# ESP-12S.net
KiCad netlist of a schematic drawn in Altium Designer
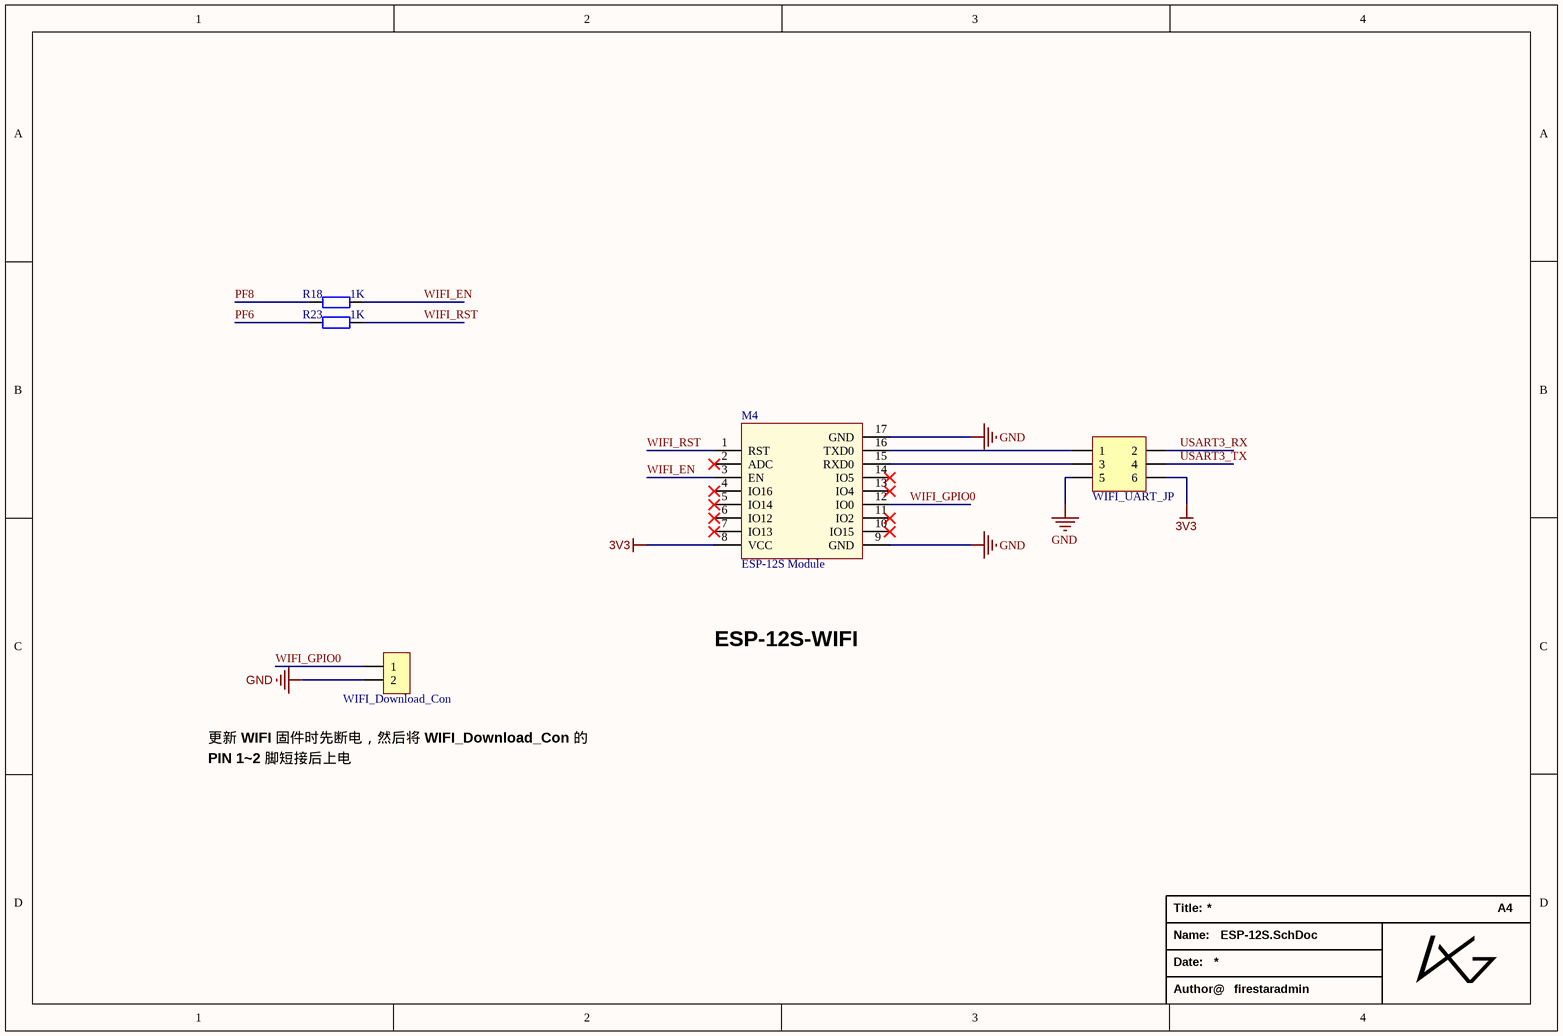
[diagram p0: ESP-12S.SchDoc]

(export (version "E")
  (design (tool "Eeschema 10.0.6"))
  (components
    (comp (ref "M4")
      (value "ESP-12S Module")
      (footprint "ESP-12S Module")
      (libsource (lib "ESP-12S Module") (part "ESP-12S Module"))
    )
    (comp (ref "R18")
      (value "1K")
      (footprint "R 0603_M")
      (description "Resistor")
      (libsource (lib "General") (part "RES"))
    )
    (comp (ref "R23")
      (value "1K")
      (footprint "R 0603_M")
      (description "Resistor")
      (libsource (lib "General") (part "RES"))
    )
    (comp (ref "WIFI_Download_Con")
      (value "HDR-1X2")
      (footprint "HDR2.54-LI-2P")
      (description "2P接插件")
      (fields (field (name "版权归属") "源创客"))
      (libsource (lib "SCH-接插件-脚距2.54") (part "Header 2"))
    )
    (comp (ref "WIFI_UART_JP")
      (value "Header3X2")
      (footprint "HDR2.54-LI-2x3P")
      (description "3*2P接插件")
      (fields (field (name "版权归属") "源创客"))
      (libsource (lib "SCH-接插件-脚距2.54") (part "Header 3X2"))
    )
  )
  (nets
    (net (code "1") (name "/PF6") (class "Default")
      (node (ref "R23") (pin "2") (pinfunction "2_2") (pintype "passive"))
    )
    (net (code "2") (name "/PF8") (class "Default")
      (node (ref "R18") (pin "2") (pinfunction "2_2") (pintype "passive"))
    )
    (net (code "3") (name "/USART3_RX") (class "Default")
      (node (ref "WIFI_UART_JP") (pin "2") (pinfunction "2_2") (pintype "passive"))
    )
    (net (code "4") (name "/USART3_TX") (class "Default")
      (node (ref "WIFI_UART_JP") (pin "4") (pinfunction "4_4") (pintype "passive"))
    )
    (net (code "5") (name "/WIFI_EN") (class "Default")
      (node (ref "M4") (pin "3") (pinfunction "EN_3") (pintype "passive"))
      (node (ref "R18") (pin "1") (pinfunction "1_1") (pintype "passive"))
    )
    (net (code "6") (name "/WIFI_GPIO0") (class "Default")
      (node (ref "M4") (pin "12") (pinfunction "IO0_12") (pintype "passive"))
      (node (ref "WIFI_Download_Con") (pin "1") (pinfunction "1_1") (pintype "passive"))
    )
    (net (code "7") (name "/WIFI_RST") (class "Default")
      (node (ref "M4") (pin "1") (pinfunction "RST_1") (pintype "passive"))
      (node (ref "R23") (pin "1") (pinfunction "1_1") (pintype "passive"))
    )
    (net (code "8") (name "3V3") (class "Default")
      (node (ref "M4") (pin "8") (pinfunction "VCC_8") (pintype "passive"))
      (node (ref "WIFI_UART_JP") (pin "6") (pinfunction "6_6") (pintype "passive"))
    )
    (net (code "9") (name "GND") (class "Default")
      (node (ref "M4") (pin "17") (pinfunction "GND_17") (pintype "passive"))
      (node (ref "M4") (pin "9") (pinfunction "GND_9") (pintype "passive"))
      (node (ref "WIFI_Download_Con") (pin "2") (pinfunction "2_2") (pintype "passive"))
      (node (ref "WIFI_UART_JP") (pin "5") (pinfunction "5_5") (pintype "passive"))
    )
    (net (code "10") (name "Net-(M4-RXD0)") (class "Default")
      (node (ref "M4") (pin "15") (pinfunction "RXD0_15") (pintype "passive"))
      (node (ref "WIFI_UART_JP") (pin "3") (pinfunction "3_3") (pintype "passive"))
    )
    (net (code "11") (name "Net-(M4-TXD0)") (class "Default")
      (node (ref "M4") (pin "16") (pinfunction "TXD0_16") (pintype "passive"))
      (node (ref "WIFI_UART_JP") (pin "1") (pinfunction "1_1") (pintype "passive"))
    )
    (net (code "12") (name "unconnected-(M4-ADC-Pad2)") (class "Default")
      (node (ref "M4") (pin "2") (pinfunction "ADC_2") (pintype "passive+no_connect"))
    )
    (net (code "13") (name "unconnected-(M4-IO2-Pad11)") (class "Default")
      (node (ref "M4") (pin "11") (pinfunction "IO2_11") (pintype "passive+no_connect"))
    )
    (net (code "14") (name "unconnected-(M4-IO4-Pad13)") (class "Default")
      (node (ref "M4") (pin "13") (pinfunction "IO4_13") (pintype "passive+no_connect"))
    )
    (net (code "15") (name "unconnected-(M4-IO5-Pad14)") (class "Default")
      (node (ref "M4") (pin "14") (pinfunction "IO5_14") (pintype "passive+no_connect"))
    )
    (net (code "16") (name "unconnected-(M4-IO12-Pad6)") (class "Default")
      (node (ref "M4") (pin "6") (pinfunction "IO12_6") (pintype "passive+no_connect"))
    )
    (net (code "17") (name "unconnected-(M4-IO13-Pad7)") (class "Default")
      (node (ref "M4") (pin "7") (pinfunction "IO13_7") (pintype "passive+no_connect"))
    )
    (net (code "18") (name "unconnected-(M4-IO14-Pad5)") (class "Default")
      (node (ref "M4") (pin "5") (pinfunction "IO14_5") (pintype "passive+no_connect"))
    )
    (net (code "19") (name "unconnected-(M4-IO15-Pad10)") (class "Default")
      (node (ref "M4") (pin "10") (pinfunction "IO15_10") (pintype "passive+no_connect"))
    )
    (net (code "20") (name "unconnected-(M4-IO16-Pad4)") (class "Default")
      (node (ref "M4") (pin "4") (pinfunction "IO16_4") (pintype "passive+no_connect"))
    )
  )
)
